# WSN_project_Gateway.net
KiCad netlist of a schematic drawn in Altium Designer
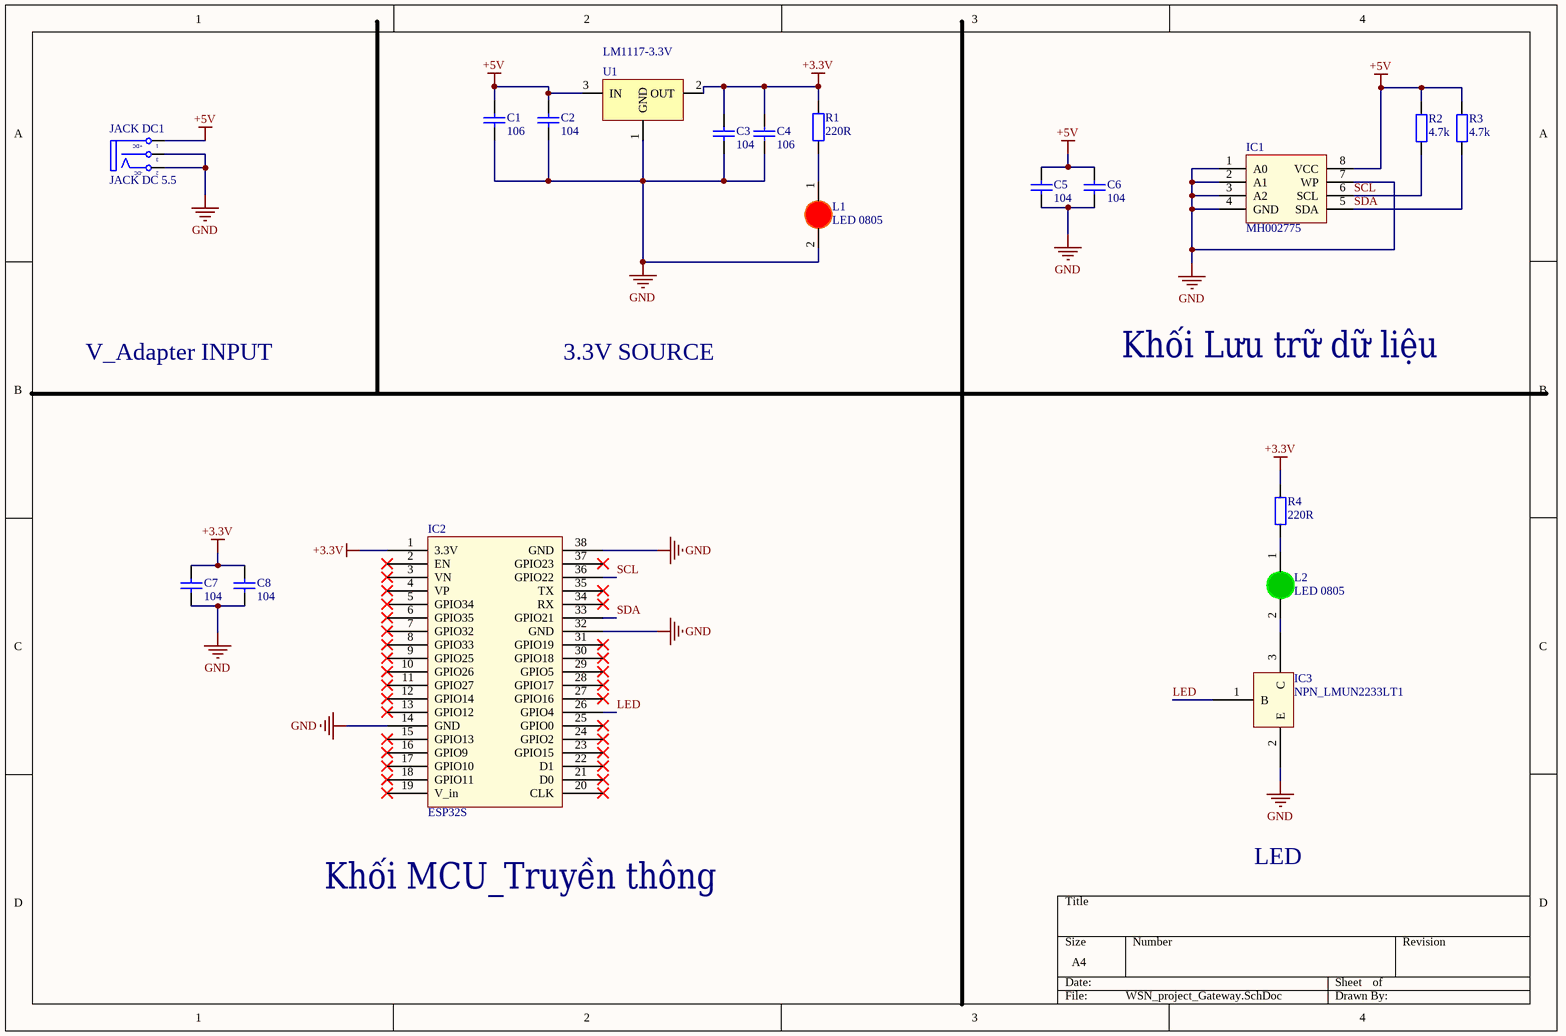
[diagram p0: WSN_project_Gateway.SchDoc]

(export (version "E")
  (design (tool "Eeschema 10.0.6"))
  (components
    (comp (ref "C1")
      (value "106")
      (footprint "tu 1206")
      (description "Dán")
      (libsource (lib "Altium_Lib_by_KhueNguyenCreator") (part "Tu 1206 106 16V 20%"))
    )
    (comp (ref "C2")
      (value "104")
      (footprint "tu 1206")
      (description "Dán")
      (libsource (lib "Altium_Lib_by_KhueNguyenCreator") (part "Tu 1206 104 50V 20%"))
    )
    (comp (ref "C3")
      (value "104")
      (footprint "tu 1206")
      (description "Dán")
      (libsource (lib "Altium_Lib_by_KhueNguyenCreator") (part "Tu 1206 104 50V 20%"))
    )
    (comp (ref "C4")
      (value "106")
      (footprint "tu 1206")
      (description "Dán")
      (libsource (lib "Altium_Lib_by_KhueNguyenCreator") (part "Tu 1206 106 16V 20%"))
    )
    (comp (ref "C5")
      (value "104")
      (footprint "tu 1206")
      (description "Dán")
      (libsource (lib "Altium_Lib_by_KhueNguyenCreator") (part "Tu 1206 104 50V 20%"))
    )
    (comp (ref "C6")
      (value "104")
      (footprint "tu 1206")
      (description "Dán")
      (libsource (lib "Altium_Lib_by_KhueNguyenCreator") (part "Tu 1206 104 50V 20%"))
    )
    (comp (ref "C7")
      (value "104")
      (footprint "tu 1206")
      (description "Dán")
      (libsource (lib "Altium_Lib_by_KhueNguyenCreator") (part "Tu 1206 104 50V 20%"))
    )
    (comp (ref "C8")
      (value "104")
      (footprint "tu 1206")
      (description "Dán")
      (libsource (lib "Altium_Lib_by_KhueNguyenCreator") (part "Tu 1206 104 50V 20%"))
    )
    (comp (ref "IC1")
      (value "MH002775")
      (footprint "DIP8")
      (description "Cắm")
      (libsource (lib "Altium_Lib_by_KhueNguyenCreator") (part "AT24C01 DIP8 EEPROM"))
    )
    (comp (ref "IC2") (value "ESP32S") (footprint "ESP32 DEVKIT") (libsource (lib "Schlib3") (part "ESP32S")))
    (comp (ref "IC3")
      (value "NPN_LMUN2233LT1")
      (footprint "SOT23_LMUN2233_trans")
      (libsource (lib "Schlib4") (part "NPN_LMUN2233LT1"))
    )
    (comp (ref "JACK DC1")
      (value "JACK DC 5.5")
      (footprint "JACK DC 5.5")
      (libsource (lib "Altium_Lib_by_KhueNguyenCreator") (part "JACK DC 5.5"))
    )
    (comp (ref "L1")
      (value "LED 0805")
      (footprint "LED-0805-Red")
      (description "Dán")
      (libsource (lib "Altium_Lib_by_KhueNguyenCreator") (part "LED 0805 Do"))
    )
    (comp (ref "L2")
      (value "LED 0805")
      (footprint "LED-1206-Green")
      (description "Dán")
      (libsource (lib "Altium_Lib_by_KhueNguyenCreator") (part "LED 1206 Xanh La"))
    )
    (comp (ref "R1")
      (value "220R")
      (footprint "tro smd 0805")
      (description "Dán")
      (libsource (lib "Altium_Lib_by_KhueNguyenCreator") (part "Tro 0805 1% 0.5R"))
    )
    (comp (ref "R2")
      (value "4.7k")
      (footprint "tro smd 0805")
      (description "Dán")
      (libsource (lib "Altium_Lib_by_KhueNguyenCreator") (part "Tro 0805 5% 4.7k"))
    )
    (comp (ref "R3")
      (value "4.7k")
      (footprint "tro smd 0805")
      (description "Dán")
      (libsource (lib "Altium_Lib_by_KhueNguyenCreator") (part "Tro 0805 5% 4.7k"))
    )
    (comp (ref "R4")
      (value "220R")
      (footprint "tro smd 0805")
      (description "Dán")
      (libsource (lib "Altium_Lib_by_KhueNguyenCreator") (part "Tro 0805 5% 220R"))
    )
    (comp (ref "U1")
      (value "LM1117-3.3V")
      (footprint "LM1117-SOP")
      (description "800mA Low-Dropout Linear Regulator")
      (fields (field (name "CREATOR") "Nguyen Ba Bien"))
      (libsource (lib "My library altium") (part "LM1117"))
    )
  )
  (nets
    (net (code "1") (name "+3.3V") (class "Default")
      (node (ref "C3") (pin "1") (pinfunction "1_1") (pintype "passive"))
      (node (ref "C4") (pin "2") (pinfunction "2_2") (pintype "passive"))
      (node (ref "C7") (pin "1") (pinfunction "1_1") (pintype "passive"))
      (node (ref "C8") (pin "1") (pinfunction "1_1") (pintype "passive"))
      (node (ref "IC2") (pin "1") (pinfunction "3.3V_1") (pintype "passive"))
      (node (ref "R1") (pin "1") (pinfunction "1_1") (pintype "passive"))
      (node (ref "R4") (pin "2") (pinfunction "2_2") (pintype "passive"))
      (node (ref "U1") (pin "2") (pinfunction "OUT_2") (pintype "passive"))
    )
    (net (code "2") (name "+5V") (class "Default")
      (node (ref "C1") (pin "2") (pinfunction "2_2") (pintype "passive"))
      (node (ref "C2") (pin "1") (pinfunction "1_1") (pintype "passive"))
      (node (ref "C5") (pin "1") (pinfunction "1_1") (pintype "passive"))
      (node (ref "C6") (pin "1") (pinfunction "1_1") (pintype "passive"))
      (node (ref "IC1") (pin "8") (pinfunction "VCC_8") (pintype "power_in"))
      (node (ref "JACK DC1") (pin "1") (pinfunction "T_1") (pintype "passive"))
      (node (ref "R2") (pin "2") (pinfunction "2_2") (pintype "passive"))
      (node (ref "R3") (pin "2") (pinfunction "2_2") (pintype "passive"))
      (node (ref "U1") (pin "3") (pinfunction "IN_3") (pintype "passive"))
    )
    (net (code "3") (name "/LED") (class "Default")
      (node (ref "IC2") (pin "26") (pinfunction "GPIO4_26") (pintype "passive"))
      (node (ref "IC3") (pin "1") (pinfunction "B_1") (pintype "passive"))
    )
    (net (code "4") (name "/SCL") (class "Default")
      (node (ref "IC1") (pin "6") (pinfunction "SCL_6") (pintype "passive"))
      (node (ref "IC2") (pin "36") (pinfunction "GPIO22_36") (pintype "passive"))
      (node (ref "R2") (pin "1") (pinfunction "1_1") (pintype "passive"))
    )
    (net (code "5") (name "/SDA") (class "Default")
      (node (ref "IC1") (pin "5") (pinfunction "SDA_5") (pintype "passive"))
      (node (ref "IC2") (pin "33") (pinfunction "GPIO21_33") (pintype "passive"))
      (node (ref "R3") (pin "1") (pinfunction "1_1") (pintype "passive"))
    )
    (net (code "6") (name "GND") (class "Default")
      (node (ref "C1") (pin "1") (pinfunction "1_1") (pintype "passive"))
      (node (ref "C2") (pin "2") (pinfunction "2_2") (pintype "passive"))
      (node (ref "C3") (pin "2") (pinfunction "2_2") (pintype "passive"))
      (node (ref "C4") (pin "1") (pinfunction "1_1") (pintype "passive"))
      (node (ref "C5") (pin "2") (pinfunction "2_2") (pintype "passive"))
      (node (ref "C6") (pin "2") (pinfunction "2_2") (pintype "passive"))
      (node (ref "C7") (pin "2") (pinfunction "2_2") (pintype "passive"))
      (node (ref "C8") (pin "2") (pinfunction "2_2") (pintype "passive"))
      (node (ref "IC1") (pin "1") (pinfunction "A0_1") (pintype "passive"))
      (node (ref "IC1") (pin "2") (pinfunction "A1_2") (pintype "passive"))
      (node (ref "IC1") (pin "3") (pinfunction "A2_3") (pintype "passive"))
      (node (ref "IC1") (pin "4") (pinfunction "GND_4") (pintype "power_in"))
      (node (ref "IC1") (pin "7") (pinfunction "WP_7") (pintype "passive"))
      (node (ref "IC2") (pin "14") (pinfunction "GND_14") (pintype "passive"))
      (node (ref "IC2") (pin "32") (pinfunction "GND_32") (pintype "passive"))
      (node (ref "IC2") (pin "38") (pinfunction "GND_38") (pintype "passive"))
      (node (ref "IC3") (pin "2") (pinfunction "E_2") (pintype "passive"))
      (node (ref "JACK DC1") (pin "2") (pinfunction "TN_2") (pintype "passive"))
      (node (ref "JACK DC1") (pin "3") (pinfunction "S_3") (pintype "power_in"))
      (node (ref "L1") (pin "2") (pinfunction "K_2") (pintype "passive"))
      (node (ref "U1") (pin "1") (pinfunction "GND_1") (pintype "passive"))
    )
    (net (code "7") (name "Net-(IC3-C)") (class "Default")
      (node (ref "IC3") (pin "3") (pinfunction "C_3") (pintype "passive"))
      (node (ref "L2") (pin "2") (pinfunction "K_2") (pintype "passive"))
    )
    (net (code "8") (name "Net-(L1-A)") (class "Default")
      (node (ref "L1") (pin "1") (pinfunction "A_1") (pintype "passive"))
      (node (ref "R1") (pin "2") (pinfunction "2_2") (pintype "passive"))
    )
    (net (code "9") (name "Net-(L2-A)") (class "Default")
      (node (ref "L2") (pin "1") (pinfunction "A_1") (pintype "passive"))
      (node (ref "R4") (pin "1") (pinfunction "1_1") (pintype "passive"))
    )
    (net (code "10") (name "unconnected-(IC2-CLK-Pad20)") (class "Default")
      (node (ref "IC2") (pin "20") (pinfunction "CLK_20") (pintype "passive+no_connect"))
    )
    (net (code "11") (name "unconnected-(IC2-D0-Pad21)") (class "Default")
      (node (ref "IC2") (pin "21") (pinfunction "D0_21") (pintype "passive+no_connect"))
    )
    (net (code "12") (name "unconnected-(IC2-D1-Pad22)") (class "Default")
      (node (ref "IC2") (pin "22") (pinfunction "D1_22") (pintype "passive+no_connect"))
    )
    (net (code "13") (name "unconnected-(IC2-EN-Pad2)") (class "Default")
      (node (ref "IC2") (pin "2") (pinfunction "EN_2") (pintype "passive+no_connect"))
    )
    (net (code "14") (name "unconnected-(IC2-GPIO0-Pad25)") (class "Default")
      (node (ref "IC2") (pin "25") (pinfunction "GPIO0_25") (pintype "passive+no_connect"))
    )
    (net (code "15") (name "unconnected-(IC2-GPIO2-Pad24)") (class "Default")
      (node (ref "IC2") (pin "24") (pinfunction "GPIO2_24") (pintype "passive+no_connect"))
    )
    (net (code "16") (name "unconnected-(IC2-GPIO5-Pad29)") (class "Default")
      (node (ref "IC2") (pin "29") (pinfunction "GPIO5_29") (pintype "passive+no_connect"))
    )
    (net (code "17") (name "unconnected-(IC2-GPIO9-Pad16)") (class "Default")
      (node (ref "IC2") (pin "16") (pinfunction "GPIO9_16") (pintype "passive+no_connect"))
    )
    (net (code "18") (name "unconnected-(IC2-GPIO10-Pad17)") (class "Default")
      (node (ref "IC2") (pin "17") (pinfunction "GPIO10_17") (pintype "passive+no_connect"))
    )
    (net (code "19") (name "unconnected-(IC2-GPIO11-Pad18)") (class "Default")
      (node (ref "IC2") (pin "18") (pinfunction "GPIO11_18") (pintype "passive+no_connect"))
    )
    (net (code "20") (name "unconnected-(IC2-GPIO12-Pad13)") (class "Default")
      (node (ref "IC2") (pin "13") (pinfunction "GPIO12_13") (pintype "passive+no_connect"))
    )
    (net (code "21") (name "unconnected-(IC2-GPIO13-Pad15)") (class "Default")
      (node (ref "IC2") (pin "15") (pinfunction "GPIO13_15") (pintype "passive+no_connect"))
    )
    (net (code "22") (name "unconnected-(IC2-GPIO14-Pad12)") (class "Default")
      (node (ref "IC2") (pin "12") (pinfunction "GPIO14_12") (pintype "passive+no_connect"))
    )
    (net (code "23") (name "unconnected-(IC2-GPIO15-Pad23)") (class "Default")
      (node (ref "IC2") (pin "23") (pinfunction "GPIO15_23") (pintype "passive+no_connect"))
    )
    (net (code "24") (name "unconnected-(IC2-GPIO16-Pad27)") (class "Default")
      (node (ref "IC2") (pin "27") (pinfunction "GPIO16_27") (pintype "passive+no_connect"))
    )
    (net (code "25") (name "unconnected-(IC2-GPIO17-Pad28)") (class "Default")
      (node (ref "IC2") (pin "28") (pinfunction "GPIO17_28") (pintype "passive+no_connect"))
    )
    (net (code "26") (name "unconnected-(IC2-GPIO18-Pad30)") (class "Default")
      (node (ref "IC2") (pin "30") (pinfunction "GPIO18_30") (pintype "passive+no_connect"))
    )
    (net (code "27") (name "unconnected-(IC2-GPIO19-Pad31)") (class "Default")
      (node (ref "IC2") (pin "31") (pinfunction "GPIO19_31") (pintype "passive+no_connect"))
    )
    (net (code "28") (name "unconnected-(IC2-GPIO23-Pad37)") (class "Default")
      (node (ref "IC2") (pin "37") (pinfunction "GPIO23_37") (pintype "passive+no_connect"))
    )
    (net (code "29") (name "unconnected-(IC2-GPIO25-Pad9)") (class "Default")
      (node (ref "IC2") (pin "9") (pinfunction "GPIO25_9") (pintype "passive+no_connect"))
    )
    (net (code "30") (name "unconnected-(IC2-GPIO26-Pad10)") (class "Default")
      (node (ref "IC2") (pin "10") (pinfunction "GPIO26_10") (pintype "passive+no_connect"))
    )
    (net (code "31") (name "unconnected-(IC2-GPIO27-Pad11)") (class "Default")
      (node (ref "IC2") (pin "11") (pinfunction "GPIO27_11") (pintype "passive+no_connect"))
    )
    (net (code "32") (name "unconnected-(IC2-GPIO32-Pad7)") (class "Default")
      (node (ref "IC2") (pin "7") (pinfunction "GPIO32_7") (pintype "passive+no_connect"))
    )
    (net (code "33") (name "unconnected-(IC2-GPIO33-Pad8)") (class "Default")
      (node (ref "IC2") (pin "8") (pinfunction "GPIO33_8") (pintype "passive+no_connect"))
    )
    (net (code "34") (name "unconnected-(IC2-GPIO34-Pad5)") (class "Default")
      (node (ref "IC2") (pin "5") (pinfunction "GPIO34_5") (pintype "passive+no_connect"))
    )
    (net (code "35") (name "unconnected-(IC2-GPIO35-Pad6)") (class "Default")
      (node (ref "IC2") (pin "6") (pinfunction "GPIO35_6") (pintype "passive+no_connect"))
    )
    (net (code "36") (name "unconnected-(IC2-RX-Pad34)") (class "Default")
      (node (ref "IC2") (pin "34") (pinfunction "RX_34") (pintype "passive+no_connect"))
    )
    (net (code "37") (name "unconnected-(IC2-TX-Pad35)") (class "Default")
      (node (ref "IC2") (pin "35") (pinfunction "TX_35") (pintype "passive+no_connect"))
    )
    (net (code "38") (name "unconnected-(IC2-VN-Pad3)") (class "Default")
      (node (ref "IC2") (pin "3") (pinfunction "VN_3") (pintype "passive+no_connect"))
    )
    (net (code "39") (name "unconnected-(IC2-VP-Pad4)") (class "Default")
      (node (ref "IC2") (pin "4") (pinfunction "VP_4") (pintype "passive+no_connect"))
    )
    (net (code "40") (name "unconnected-(IC2-V_in-Pad19)") (class "Default")
      (node (ref "IC2") (pin "19") (pinfunction "V_in_19") (pintype "passive+no_connect"))
    )
  )
)
